# SOIC-28_v10.net
KiCad netlist of a schematic drawn in EAGLE
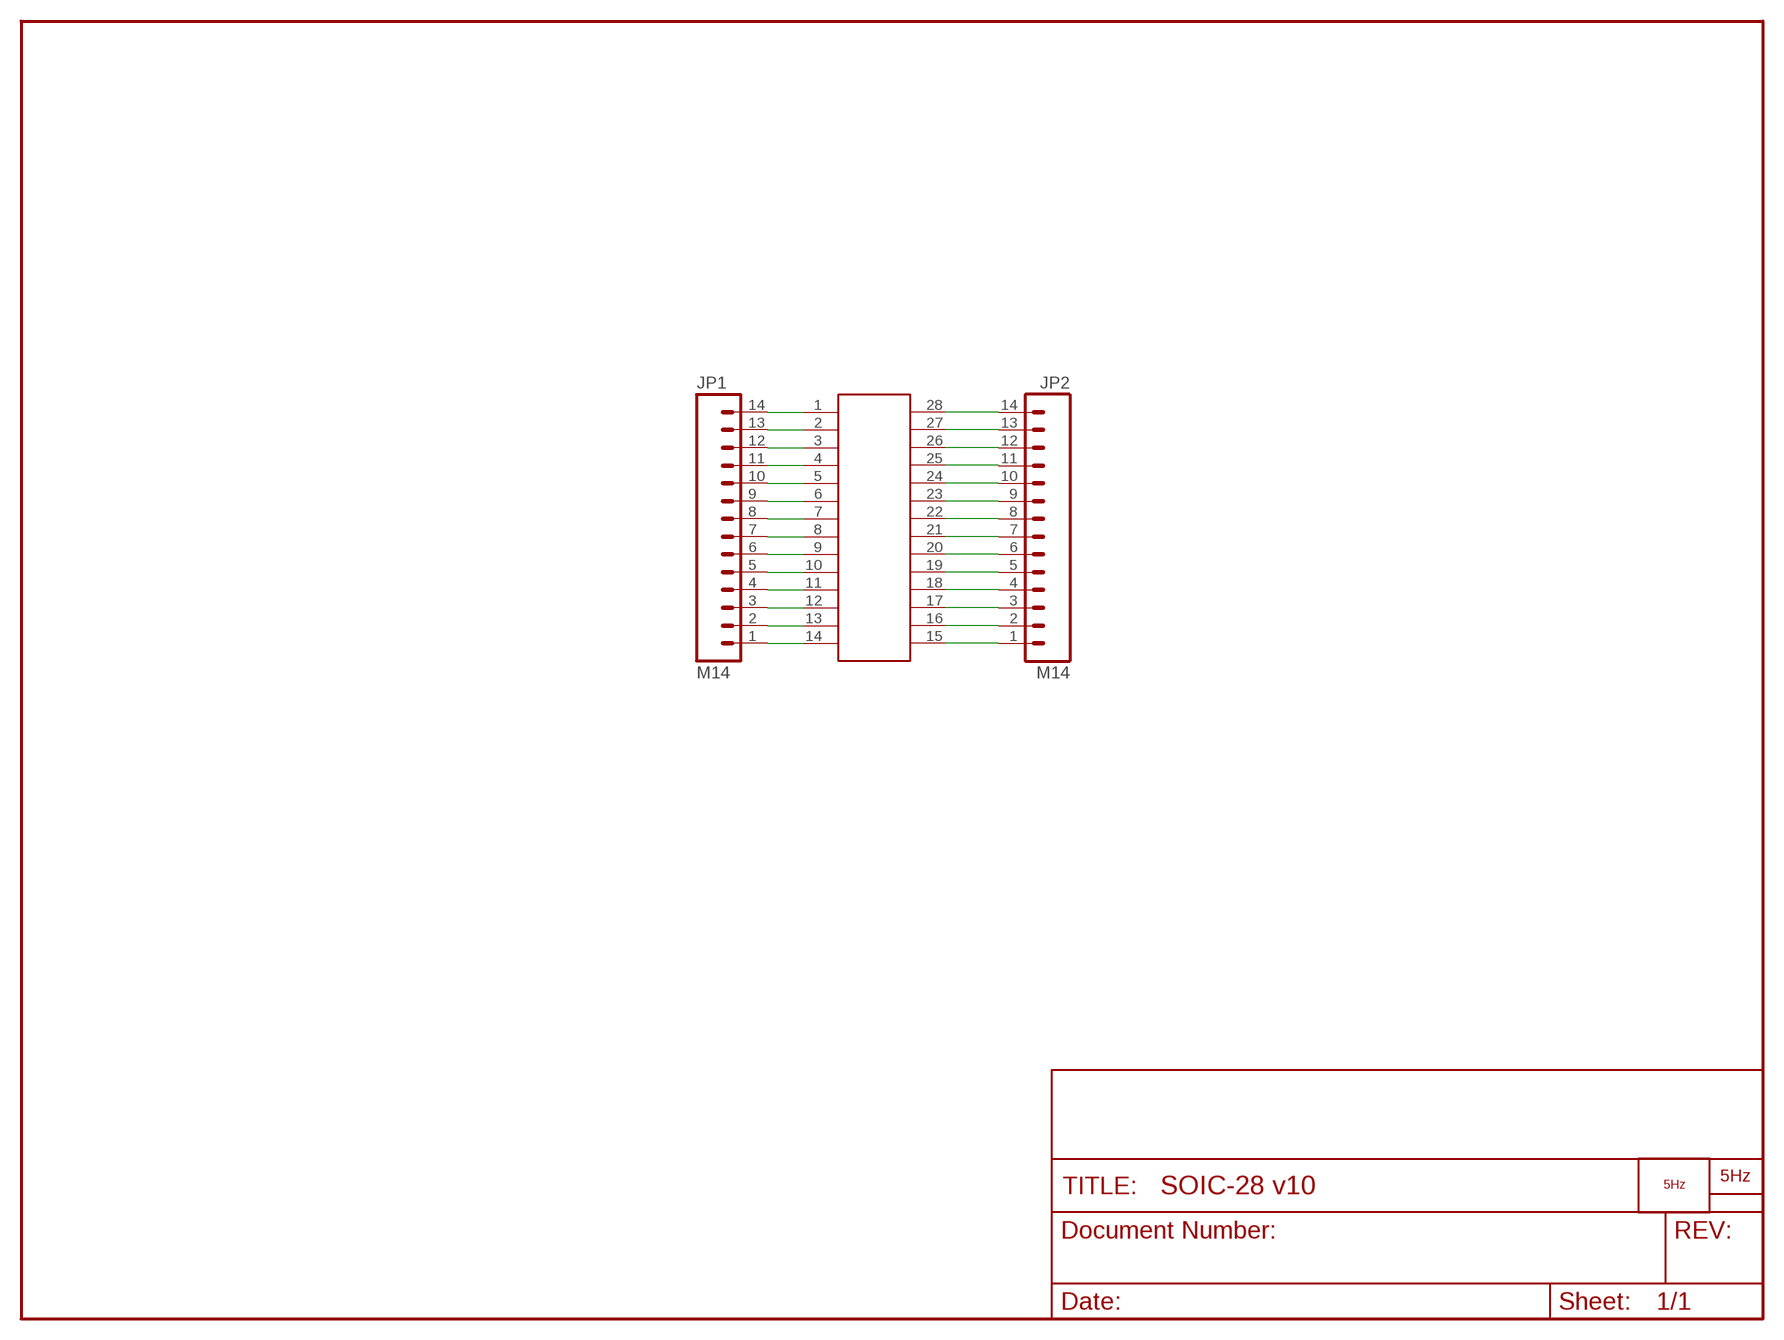
[diagram p0: schematic, sheet 1]

(export (version "E")
  (design (tool "Eeschema 10.0.6"))
  (components
    (comp (ref "JP1")
      (value "M14")
      (footprint "eagle-import:1X14")
      (libsource (lib "eagle-import") (part "M14"))
    )
    (comp (ref "JP2")
      (value "M14")
      (footprint "eagle-import:1X14")
      (libsource (lib "eagle-import") (part "M14"))
    )
    (comp (ref "LOGO1")
      (value "LOGO_5HZ_MAIN_5MM")
      (footprint "eagle-import:5HZ_LOGO_MAIN_5MM")
      (libsource (lib "eagle-import") (part "LOGO_5HZ_MAIN_5MM"))
    )
    (comp (ref "U$1")
      (value "SOIC-28SOIC-28")
      (footprint "eagle-import:SOIC-28")
      (libsource (lib "eagle-import") (part "SOIC-28SOIC-28"))
    )
    (comp (ref "U$2")
      (value "LOGO2_SILK10MM")
      (footprint "eagle-import:LOGO2_10MM")
      (libsource (lib "eagle-import") (part "LOGO2_SILK10MM"))
    )
  )
  (nets
    (net (code "1") (name "Net-(U$1-P$1)") (class "Default")
      (node (ref "JP1") (pin "14") (pinfunction "14_14") (pintype "passive"))
      (node (ref "U$1") (pin "1") (pinfunction "P$1_1") (pintype "bidirectional"))
    )
    (net (code "2") (name "Net-(U$1-P$2)") (class "Default")
      (node (ref "JP1") (pin "13") (pinfunction "13_13") (pintype "passive"))
      (node (ref "U$1") (pin "2") (pinfunction "P$2_2") (pintype "bidirectional"))
    )
    (net (code "3") (name "Net-(U$1-P$3)") (class "Default")
      (node (ref "JP1") (pin "12") (pinfunction "12_12") (pintype "passive"))
      (node (ref "U$1") (pin "3") (pinfunction "P$3_3") (pintype "bidirectional"))
    )
    (net (code "4") (name "Net-(U$1-P$4)") (class "Default")
      (node (ref "JP1") (pin "11") (pinfunction "11_11") (pintype "passive"))
      (node (ref "U$1") (pin "4") (pinfunction "P$4_4") (pintype "bidirectional"))
    )
    (net (code "5") (name "Net-(U$1-P$5)") (class "Default")
      (node (ref "JP1") (pin "10") (pinfunction "10_10") (pintype "passive"))
      (node (ref "U$1") (pin "5") (pinfunction "P$5_5") (pintype "bidirectional"))
    )
    (net (code "6") (name "Net-(U$1-P$6)") (class "Default")
      (node (ref "JP1") (pin "9") (pinfunction "9_9") (pintype "passive"))
      (node (ref "U$1") (pin "6") (pinfunction "P$6_6") (pintype "bidirectional"))
    )
    (net (code "7") (name "Net-(U$1-P$7)") (class "Default")
      (node (ref "JP1") (pin "8") (pinfunction "8_8") (pintype "passive"))
      (node (ref "U$1") (pin "7") (pinfunction "P$7_7") (pintype "bidirectional"))
    )
    (net (code "8") (name "Net-(U$1-P$8)") (class "Default")
      (node (ref "JP1") (pin "7") (pinfunction "7_7") (pintype "passive"))
      (node (ref "U$1") (pin "8") (pinfunction "P$8_8") (pintype "bidirectional"))
    )
    (net (code "9") (name "Net-(U$1-P$9)") (class "Default")
      (node (ref "JP1") (pin "6") (pinfunction "6_6") (pintype "passive"))
      (node (ref "U$1") (pin "9") (pinfunction "P$9_9") (pintype "bidirectional"))
    )
    (net (code "10") (name "Net-(U$1-P$10)") (class "Default")
      (node (ref "JP1") (pin "5") (pinfunction "5_5") (pintype "passive"))
      (node (ref "U$1") (pin "10") (pinfunction "P$10_10") (pintype "bidirectional"))
    )
    (net (code "11") (name "Net-(U$1-P$11)") (class "Default")
      (node (ref "JP1") (pin "4") (pinfunction "4_4") (pintype "passive"))
      (node (ref "U$1") (pin "11") (pinfunction "P$11_11") (pintype "bidirectional"))
    )
    (net (code "12") (name "Net-(U$1-P$12)") (class "Default")
      (node (ref "JP1") (pin "3") (pinfunction "3_3") (pintype "passive"))
      (node (ref "U$1") (pin "12") (pinfunction "P$12_12") (pintype "bidirectional"))
    )
    (net (code "13") (name "Net-(U$1-P$13)") (class "Default")
      (node (ref "JP1") (pin "2") (pinfunction "2_2") (pintype "passive"))
      (node (ref "U$1") (pin "13") (pinfunction "P$13_13") (pintype "bidirectional"))
    )
    (net (code "14") (name "Net-(U$1-P$14)") (class "Default")
      (node (ref "JP1") (pin "1") (pinfunction "1_1") (pintype "passive"))
      (node (ref "U$1") (pin "14") (pinfunction "P$14_14") (pintype "bidirectional"))
    )
    (net (code "15") (name "Net-(U$1-P$15)") (class "Default")
      (node (ref "JP2") (pin "1") (pinfunction "1_1") (pintype "passive"))
      (node (ref "U$1") (pin "15") (pinfunction "P$15_15") (pintype "bidirectional"))
    )
    (net (code "16") (name "Net-(U$1-P$16)") (class "Default")
      (node (ref "JP2") (pin "2") (pinfunction "2_2") (pintype "passive"))
      (node (ref "U$1") (pin "16") (pinfunction "P$16_16") (pintype "bidirectional"))
    )
    (net (code "17") (name "Net-(U$1-P$17)") (class "Default")
      (node (ref "JP2") (pin "3") (pinfunction "3_3") (pintype "passive"))
      (node (ref "U$1") (pin "17") (pinfunction "P$17_17") (pintype "bidirectional"))
    )
    (net (code "18") (name "Net-(U$1-P$18)") (class "Default")
      (node (ref "JP2") (pin "4") (pinfunction "4_4") (pintype "passive"))
      (node (ref "U$1") (pin "18") (pinfunction "P$18_18") (pintype "bidirectional"))
    )
    (net (code "19") (name "Net-(U$1-P$19)") (class "Default")
      (node (ref "JP2") (pin "5") (pinfunction "5_5") (pintype "passive"))
      (node (ref "U$1") (pin "19") (pinfunction "P$19_19") (pintype "bidirectional"))
    )
    (net (code "20") (name "Net-(U$1-P$20)") (class "Default")
      (node (ref "JP2") (pin "6") (pinfunction "6_6") (pintype "passive"))
      (node (ref "U$1") (pin "20") (pinfunction "P$20_20") (pintype "bidirectional"))
    )
    (net (code "21") (name "Net-(U$1-P$21)") (class "Default")
      (node (ref "JP2") (pin "7") (pinfunction "7_7") (pintype "passive"))
      (node (ref "U$1") (pin "21") (pinfunction "P$21_21") (pintype "bidirectional"))
    )
    (net (code "22") (name "Net-(U$1-P$22)") (class "Default")
      (node (ref "JP2") (pin "8") (pinfunction "8_8") (pintype "passive"))
      (node (ref "U$1") (pin "22") (pinfunction "P$22_22") (pintype "bidirectional"))
    )
    (net (code "23") (name "Net-(U$1-P$23)") (class "Default")
      (node (ref "JP2") (pin "9") (pinfunction "9_9") (pintype "passive"))
      (node (ref "U$1") (pin "23") (pinfunction "P$23_23") (pintype "bidirectional"))
    )
    (net (code "24") (name "Net-(U$1-P$24)") (class "Default")
      (node (ref "JP2") (pin "10") (pinfunction "10_10") (pintype "passive"))
      (node (ref "U$1") (pin "24") (pinfunction "P$24_24") (pintype "bidirectional"))
    )
    (net (code "25") (name "Net-(U$1-P$25)") (class "Default")
      (node (ref "JP2") (pin "11") (pinfunction "11_11") (pintype "passive"))
      (node (ref "U$1") (pin "25") (pinfunction "P$25_25") (pintype "bidirectional"))
    )
    (net (code "26") (name "Net-(U$1-P$26)") (class "Default")
      (node (ref "JP2") (pin "12") (pinfunction "12_12") (pintype "passive"))
      (node (ref "U$1") (pin "26") (pinfunction "P$26_26") (pintype "bidirectional"))
    )
    (net (code "27") (name "Net-(U$1-P$27)") (class "Default")
      (node (ref "JP2") (pin "13") (pinfunction "13_13") (pintype "passive"))
      (node (ref "U$1") (pin "27") (pinfunction "P$27_27") (pintype "bidirectional"))
    )
    (net (code "28") (name "Net-(U$1-P$28)") (class "Default")
      (node (ref "JP2") (pin "14") (pinfunction "14_14") (pintype "passive"))
      (node (ref "U$1") (pin "28") (pinfunction "P$28_28") (pintype "bidirectional"))
    )
  )
)
